# Chassis2Smol.net
KiCad netlist of a schematic drawn in EAGLE
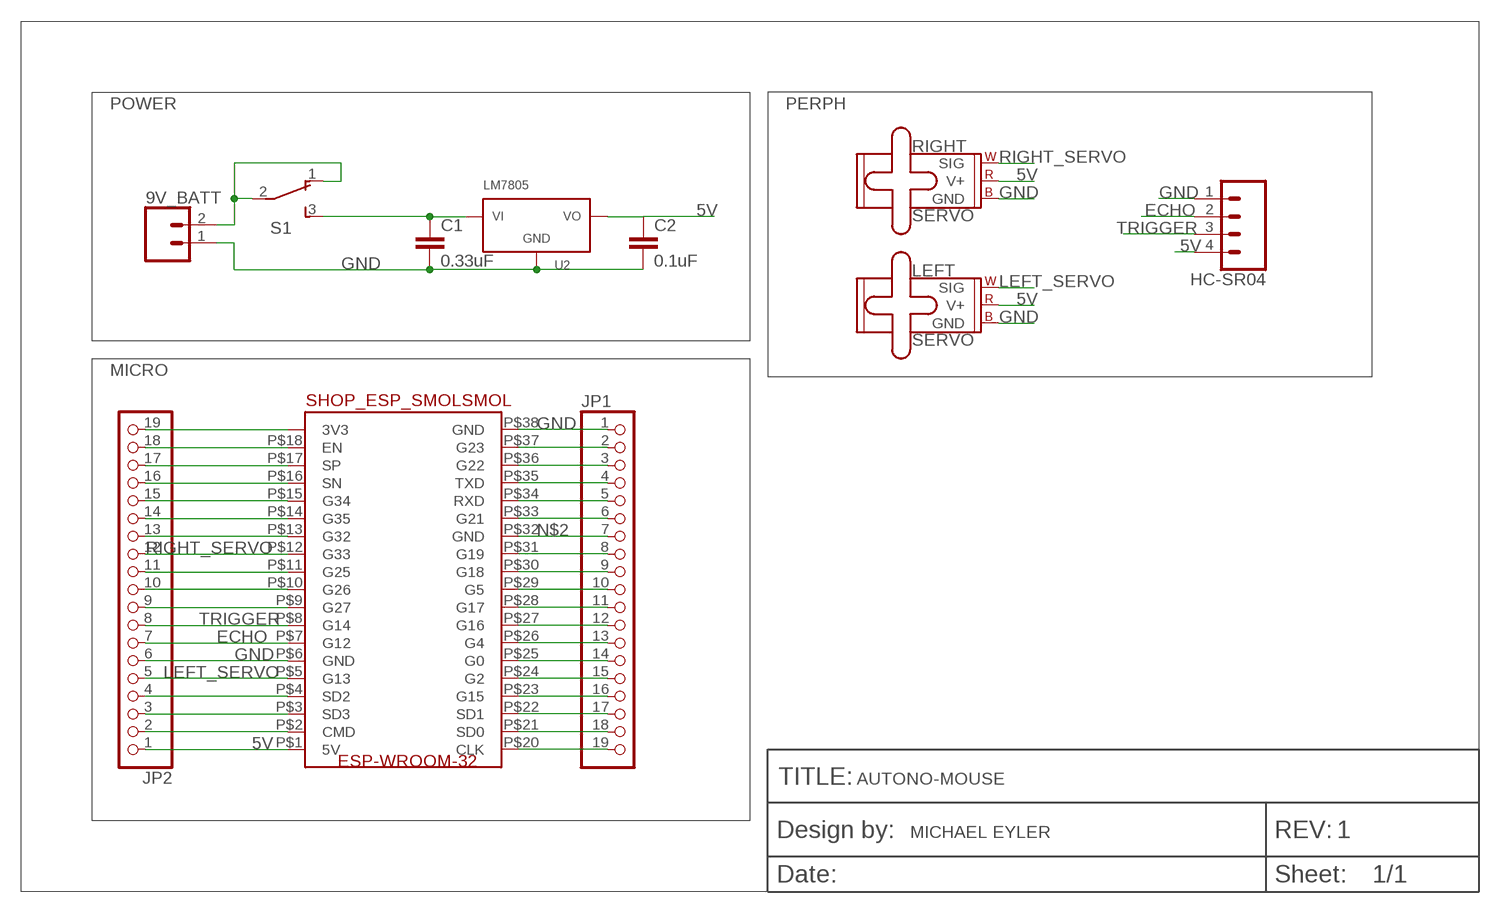
[diagram p0: schematic, sheet 1]

(export (version "E")
  (design (tool "Eeschema 10.0.6"))
  (components
    (comp (ref "9V_BATT")
      (value "CONN_02")
      (footprint "eagle-import:1X02")
      (libsource (lib "eagle-import") (part "CONN_02"))
    )
    (comp (ref "C1")
      (value "0.33uF")
      (footprint "eagle-import:CAP-PTH-SMALL-KIT")
      (libsource (lib "eagle-import") (part "0.1UF-KIT-EZ-50V-20%"))
    )
    (comp (ref "C2")
      (value "0.1uF")
      (footprint "eagle-import:CAP-PTH-SMALL-KIT")
      (libsource (lib "eagle-import") (part "0.1UF-KIT-EZ-50V-20%"))
    )
    (comp (ref "HC-SR04")
      (value "CONN_04PTH")
      (footprint "eagle-import:1X04")
      (libsource (lib "eagle-import") (part "CONN_04PTH"))
    )
    (comp (ref "JP1")
      (value "PINHD-1X19")
      (footprint "eagle-import:1X19")
      (libsource (lib "eagle-import") (part "PINHD-1X19"))
    )
    (comp (ref "JP2")
      (value "PINHD-1X19")
      (footprint "eagle-import:1X19")
      (libsource (lib "eagle-import") (part "PINHD-1X19"))
    )
    (comp (ref "LEFT")
      (value "SERVO")
      (footprint "eagle-import:1X03")
      (libsource (lib "eagle-import") (part "SERVO"))
    )
    (comp (ref "RIGHT")
      (value "SERVO")
      (footprint "eagle-import:1X03")
      (libsource (lib "eagle-import") (part "SERVO"))
    )
    (comp (ref "S1")
      (value "TL36PO")
      (footprint "eagle-import:TL3XPO")
      (libsource (lib "eagle-import") (part "TL36PO"))
    )
    (comp (ref "U$1")
      (value "FRAME-BADGE")
      (footprint "eagle-import:DUMMY")
      (libsource (lib "eagle-import") (part "FRAME-BADGE"))
    )
    (comp (ref "U$2")
      (value "SHOP_ESP_SMOLSMOL")
      (footprint "eagle-import:ESP32-WROOM-32_SMOL")
      (libsource (lib "eagle-import") (part "SHOP_ESP_SMOLSMOL"))
    )
    (comp (ref "U2")
      (value "LM7805")
      (footprint "eagle-import:TO220H")
      (libsource (lib "eagle-import") (part "LM7805"))
    )
  )
  (nets
    (net (code "1") (name "/5V") (class "Default")
      (node (ref "C2") (pin "1") (pinfunction "1_1") (pintype "passive"))
      (node (ref "HC-SR04") (pin "4") (pinfunction "4_4") (pintype "passive"))
      (node (ref "JP2") (pin "1") (pinfunction "1_1") (pintype "passive"))
      (node (ref "LEFT") (pin "2") (pinfunction "V+_2") (pintype "bidirectional"))
      (node (ref "RIGHT") (pin "2") (pinfunction "V+_2") (pintype "bidirectional"))
      (node (ref "U$2") (pin "P$1") (pinfunction "5V_P$1") (pintype "power_in"))
      (node (ref "U2") (pin "3") (pinfunction "VOUT_3") (pintype "bidirectional"))
    )
    (net (code "2") (name "/ECHO") (class "Default")
      (node (ref "HC-SR04") (pin "2") (pinfunction "2_2") (pintype "passive"))
      (node (ref "JP2") (pin "7") (pinfunction "7_7") (pintype "passive"))
      (node (ref "U$2") (pin "P$7") (pinfunction "G12_P$7") (pintype "bidirectional"))
    )
    (net (code "3") (name "/GND") (class "Default")
      (node (ref "9V_BATT") (pin "1") (pinfunction "1_1") (pintype "passive"))
      (node (ref "C1") (pin "2") (pinfunction "2_2") (pintype "passive"))
      (node (ref "C2") (pin "2") (pinfunction "2_2") (pintype "passive"))
      (node (ref "HC-SR04") (pin "1") (pinfunction "1_1") (pintype "passive"))
      (node (ref "JP1") (pin "1") (pinfunction "1_1") (pintype "passive"))
      (node (ref "JP2") (pin "6") (pinfunction "6_6") (pintype "passive"))
      (node (ref "LEFT") (pin "3") (pinfunction "GND_3") (pintype "bidirectional"))
      (node (ref "RIGHT") (pin "3") (pinfunction "GND_3") (pintype "bidirectional"))
      (node (ref "U$2") (pin "P$38") (pinfunction "GND_P$38") (pintype "bidirectional"))
      (node (ref "U$2") (pin "P$6") (pinfunction "GND_P$6") (pintype "bidirectional"))
      (node (ref "U2") (pin "2") (pinfunction "GND_2") (pintype "bidirectional"))
    )
    (net (code "4") (name "/LEFT_SERVO") (class "Default")
      (node (ref "JP2") (pin "5") (pinfunction "5_5") (pintype "passive"))
      (node (ref "LEFT") (pin "1") (pinfunction "SIG_1") (pintype "bidirectional"))
      (node (ref "U$2") (pin "P$5") (pinfunction "G13_P$5") (pintype "bidirectional"))
    )
    (net (code "5") (name "/N$2") (class "Default")
      (node (ref "JP1") (pin "7") (pinfunction "7_7") (pintype "passive"))
      (node (ref "U$2") (pin "P$32") (pinfunction "GND_P$32") (pintype "bidirectional"))
    )
    (net (code "6") (name "/RIGHT_SERVO") (class "Default")
      (node (ref "JP2") (pin "12") (pinfunction "12_12") (pintype "passive"))
      (node (ref "RIGHT") (pin "1") (pinfunction "SIG_1") (pintype "bidirectional"))
      (node (ref "U$2") (pin "P$12") (pinfunction "G33_P$12") (pintype "bidirectional"))
    )
    (net (code "7") (name "/TRIGGER") (class "Default")
      (node (ref "HC-SR04") (pin "3") (pinfunction "3_3") (pintype "passive"))
      (node (ref "JP2") (pin "8") (pinfunction "8_8") (pintype "passive"))
      (node (ref "U$2") (pin "P$8") (pinfunction "G14_P$8") (pintype "bidirectional"))
    )
    (net (code "8") (name "Net-(S1-O)") (class "Default")
      (node (ref "9V_BATT") (pin "2") (pinfunction "2_2") (pintype "passive"))
      (node (ref "S1") (pin "1") (pinfunction "O_1") (pintype "passive"))
      (node (ref "S1") (pin "2") (pinfunction "P_2") (pintype "passive"))
    )
    (net (code "9") (name "Net-(S1-S)") (class "Default")
      (node (ref "C1") (pin "1") (pinfunction "1_1") (pintype "passive"))
      (node (ref "S1") (pin "3") (pinfunction "S_3") (pintype "passive"))
      (node (ref "U2") (pin "1") (pinfunction "VIN_1") (pintype "bidirectional"))
    )
    (net (code "10") (name "Net-(U$2-3V3)") (class "Default")
      (node (ref "JP2") (pin "19") (pinfunction "19_19") (pintype "passive"))
      (node (ref "U$2") (pin "P$19") (pinfunction "3V3_P$19") (pintype "power_in"))
    )
    (net (code "11") (name "Net-(U$2-CLK)") (class "Default")
      (node (ref "JP1") (pin "19") (pinfunction "19_19") (pintype "passive"))
      (node (ref "U$2") (pin "P$20") (pinfunction "CLK_P$20") (pintype "bidirectional"))
    )
    (net (code "12") (name "Net-(U$2-CMD)") (class "Default")
      (node (ref "JP2") (pin "2") (pinfunction "2_2") (pintype "passive"))
      (node (ref "U$2") (pin "P$2") (pinfunction "CMD_P$2") (pintype "power_in"))
    )
    (net (code "13") (name "Net-(U$2-EN)") (class "Default")
      (node (ref "JP2") (pin "18") (pinfunction "18_18") (pintype "passive"))
      (node (ref "U$2") (pin "P$18") (pinfunction "EN_P$18") (pintype "bidirectional"))
    )
    (net (code "14") (name "Net-(U$2-G0)") (class "Default")
      (node (ref "JP1") (pin "14") (pinfunction "14_14") (pintype "passive"))
      (node (ref "U$2") (pin "P$25") (pinfunction "G0_P$25") (pintype "bidirectional"))
    )
    (net (code "15") (name "Net-(U$2-G2)") (class "Default")
      (node (ref "JP1") (pin "15") (pinfunction "15_15") (pintype "passive"))
      (node (ref "U$2") (pin "P$24") (pinfunction "G2_P$24") (pintype "bidirectional"))
    )
    (net (code "16") (name "Net-(U$2-G4)") (class "Default")
      (node (ref "JP1") (pin "13") (pinfunction "13_13") (pintype "passive"))
      (node (ref "U$2") (pin "P$26") (pinfunction "G4_P$26") (pintype "bidirectional"))
    )
    (net (code "17") (name "Net-(U$2-G5)") (class "Default")
      (node (ref "JP1") (pin "10") (pinfunction "10_10") (pintype "passive"))
      (node (ref "U$2") (pin "P$29") (pinfunction "G5_P$29") (pintype "bidirectional"))
    )
    (net (code "18") (name "Net-(U$2-G15)") (class "Default")
      (node (ref "JP1") (pin "16") (pinfunction "16_16") (pintype "passive"))
      (node (ref "U$2") (pin "P$23") (pinfunction "G15_P$23") (pintype "bidirectional"))
    )
    (net (code "19") (name "Net-(U$2-G16)") (class "Default")
      (node (ref "JP1") (pin "12") (pinfunction "12_12") (pintype "passive"))
      (node (ref "U$2") (pin "P$27") (pinfunction "G16_P$27") (pintype "bidirectional"))
    )
    (net (code "20") (name "Net-(U$2-G17)") (class "Default")
      (node (ref "JP1") (pin "11") (pinfunction "11_11") (pintype "passive"))
      (node (ref "U$2") (pin "P$28") (pinfunction "G17_P$28") (pintype "bidirectional"))
    )
    (net (code "21") (name "Net-(U$2-G18)") (class "Default")
      (node (ref "JP1") (pin "9") (pinfunction "9_9") (pintype "passive"))
      (node (ref "U$2") (pin "P$30") (pinfunction "G18_P$30") (pintype "bidirectional"))
    )
    (net (code "22") (name "Net-(U$2-G19)") (class "Default")
      (node (ref "JP1") (pin "8") (pinfunction "8_8") (pintype "passive"))
      (node (ref "U$2") (pin "P$31") (pinfunction "G19_P$31") (pintype "bidirectional"))
    )
    (net (code "23") (name "Net-(U$2-G21)") (class "Default")
      (node (ref "JP1") (pin "6") (pinfunction "6_6") (pintype "passive"))
      (node (ref "U$2") (pin "P$33") (pinfunction "G21_P$33") (pintype "bidirectional"))
    )
    (net (code "24") (name "Net-(U$2-G22)") (class "Default")
      (node (ref "JP1") (pin "3") (pinfunction "3_3") (pintype "passive"))
      (node (ref "U$2") (pin "P$36") (pinfunction "G22_P$36") (pintype "bidirectional"))
    )
    (net (code "25") (name "Net-(U$2-G23)") (class "Default")
      (node (ref "JP1") (pin "2") (pinfunction "2_2") (pintype "passive"))
      (node (ref "U$2") (pin "P$37") (pinfunction "G23_P$37") (pintype "bidirectional"))
    )
    (net (code "26") (name "Net-(U$2-G25)") (class "Default")
      (node (ref "JP2") (pin "11") (pinfunction "11_11") (pintype "passive"))
      (node (ref "U$2") (pin "P$11") (pinfunction "G25_P$11") (pintype "bidirectional"))
    )
    (net (code "27") (name "Net-(U$2-G26)") (class "Default")
      (node (ref "JP2") (pin "10") (pinfunction "10_10") (pintype "passive"))
      (node (ref "U$2") (pin "P$10") (pinfunction "G26_P$10") (pintype "bidirectional"))
    )
    (net (code "28") (name "Net-(U$2-G27)") (class "Default")
      (node (ref "JP2") (pin "9") (pinfunction "9_9") (pintype "passive"))
      (node (ref "U$2") (pin "P$9") (pinfunction "G27_P$9") (pintype "bidirectional"))
    )
    (net (code "29") (name "Net-(U$2-G32)") (class "Default")
      (node (ref "JP2") (pin "13") (pinfunction "13_13") (pintype "passive"))
      (node (ref "U$2") (pin "P$13") (pinfunction "G32_P$13") (pintype "bidirectional"))
    )
    (net (code "30") (name "Net-(U$2-G34)") (class "Default")
      (node (ref "JP2") (pin "15") (pinfunction "15_15") (pintype "passive"))
      (node (ref "U$2") (pin "P$15") (pinfunction "G34_P$15") (pintype "bidirectional"))
    )
    (net (code "31") (name "Net-(U$2-G35)") (class "Default")
      (node (ref "JP2") (pin "14") (pinfunction "14_14") (pintype "passive"))
      (node (ref "U$2") (pin "P$14") (pinfunction "G35_P$14") (pintype "bidirectional"))
    )
    (net (code "32") (name "Net-(U$2-RXD)") (class "Default")
      (node (ref "JP1") (pin "5") (pinfunction "5_5") (pintype "passive"))
      (node (ref "U$2") (pin "P$34") (pinfunction "RXD_P$34") (pintype "bidirectional"))
    )
    (net (code "33") (name "Net-(U$2-SD0)") (class "Default")
      (node (ref "JP1") (pin "18") (pinfunction "18_18") (pintype "passive"))
      (node (ref "U$2") (pin "P$21") (pinfunction "SD0_P$21") (pintype "bidirectional"))
    )
    (net (code "34") (name "Net-(U$2-SD1)") (class "Default")
      (node (ref "JP1") (pin "17") (pinfunction "17_17") (pintype "passive"))
      (node (ref "U$2") (pin "P$22") (pinfunction "SD1_P$22") (pintype "bidirectional"))
    )
    (net (code "35") (name "Net-(U$2-SD2)") (class "Default")
      (node (ref "JP2") (pin "4") (pinfunction "4_4") (pintype "passive"))
      (node (ref "U$2") (pin "P$4") (pinfunction "SD2_P$4") (pintype "bidirectional"))
    )
    (net (code "36") (name "Net-(U$2-SD3)") (class "Default")
      (node (ref "JP2") (pin "3") (pinfunction "3_3") (pintype "passive"))
      (node (ref "U$2") (pin "P$3") (pinfunction "SD3_P$3") (pintype "bidirectional"))
    )
    (net (code "37") (name "Net-(U$2-SN)") (class "Default")
      (node (ref "JP2") (pin "16") (pinfunction "16_16") (pintype "passive"))
      (node (ref "U$2") (pin "P$16") (pinfunction "SN_P$16") (pintype "bidirectional"))
    )
    (net (code "38") (name "Net-(U$2-SP)") (class "Default")
      (node (ref "JP2") (pin "17") (pinfunction "17_17") (pintype "passive"))
      (node (ref "U$2") (pin "P$17") (pinfunction "SP_P$17") (pintype "bidirectional"))
    )
    (net (code "39") (name "Net-(U$2-TXD)") (class "Default")
      (node (ref "JP1") (pin "4") (pinfunction "4_4") (pintype "passive"))
      (node (ref "U$2") (pin "P$35") (pinfunction "TXD_P$35") (pintype "bidirectional"))
    )
  )
)
